# ThermoActuator-v10.net
KiCad netlist of a schematic drawn in EAGLE
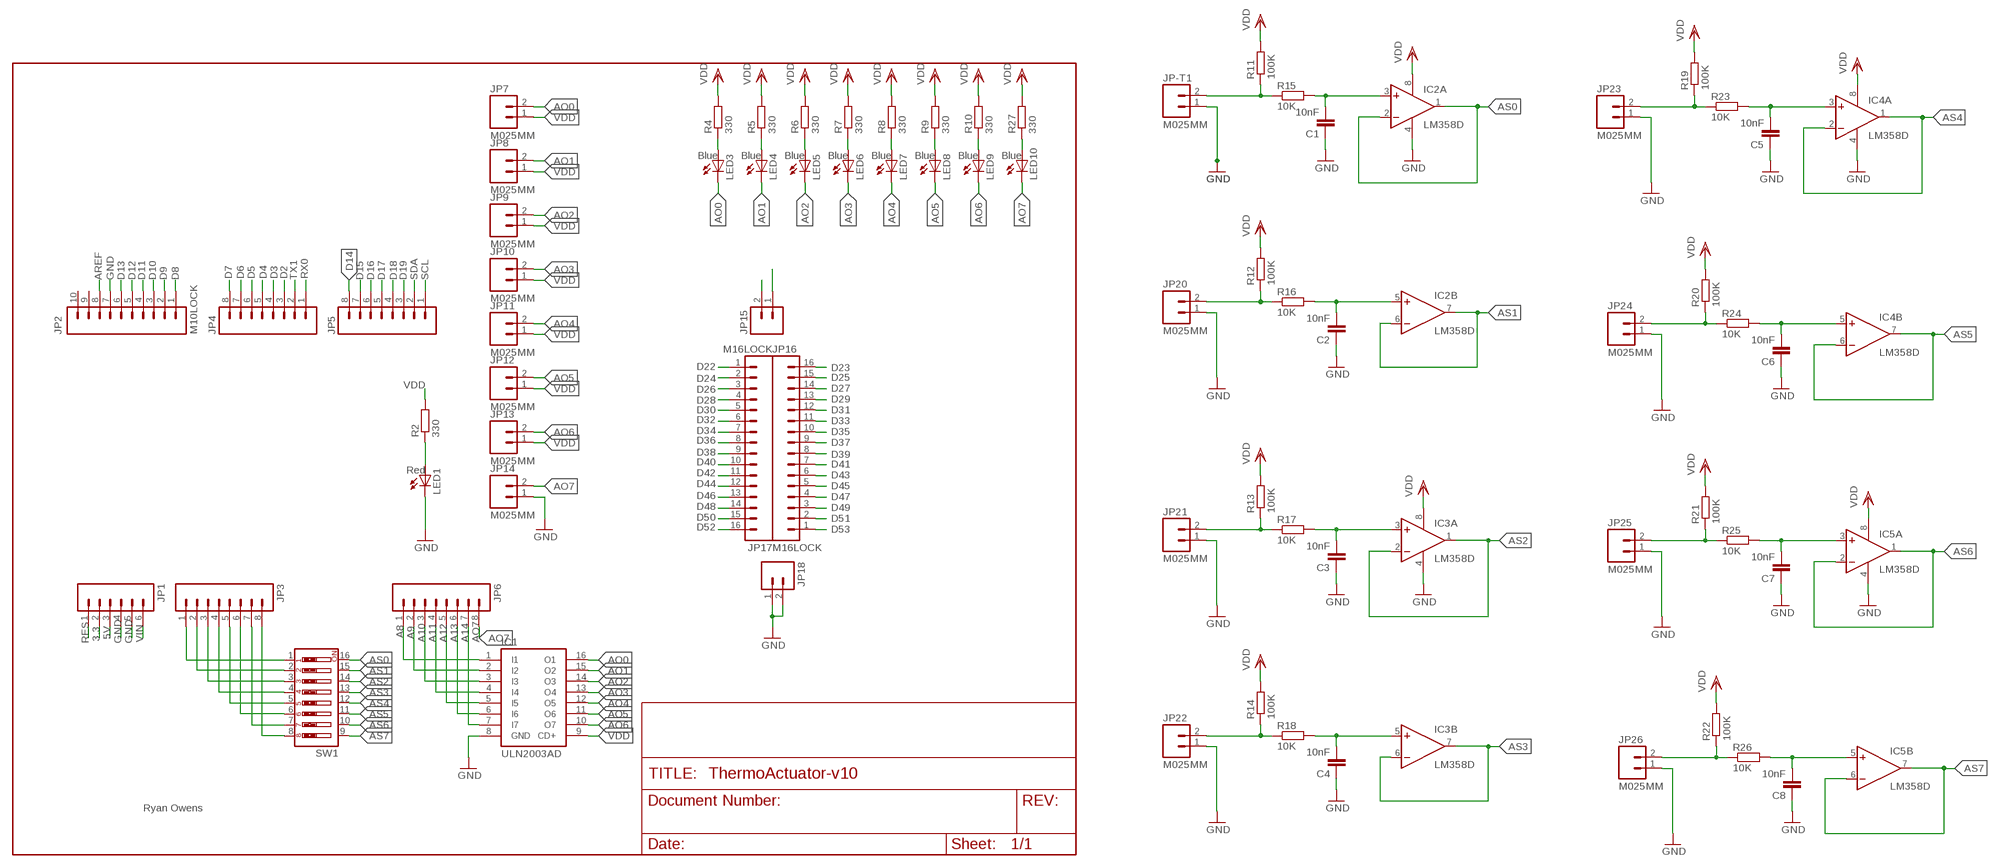
[diagram p0: schematic, sheet 1]

(export (version "E")
  (design (tool "Eeschema 10.0.6"))
  (components
    (comp (ref "C1")
      (value "10nF")
      (footprint "eagle-import:C1206")
      (libsource (lib "eagle-import") (part "C-EUC1206"))
    )
    (comp (ref "C2")
      (value "10nF")
      (footprint "eagle-import:C1206")
      (libsource (lib "eagle-import") (part "C-EUC1206"))
    )
    (comp (ref "C3")
      (value "10nF")
      (footprint "eagle-import:C1206")
      (libsource (lib "eagle-import") (part "C-EUC1206"))
    )
    (comp (ref "C4")
      (value "10nF")
      (footprint "eagle-import:C1206")
      (libsource (lib "eagle-import") (part "C-EUC1206"))
    )
    (comp (ref "C5")
      (value "10nF")
      (footprint "eagle-import:C1206")
      (libsource (lib "eagle-import") (part "C-EUC1206"))
    )
    (comp (ref "C6")
      (value "10nF")
      (footprint "eagle-import:C1206")
      (libsource (lib "eagle-import") (part "C-EUC1206"))
    )
    (comp (ref "C7")
      (value "10nF")
      (footprint "eagle-import:C1206")
      (libsource (lib "eagle-import") (part "C-EUC1206"))
    )
    (comp (ref "C8")
      (value "10nF")
      (footprint "eagle-import:C1206")
      (libsource (lib "eagle-import") (part "C-EUC1206"))
    )
    (comp (ref "IC1")
      (value "ULN2003AD")
      (footprint "eagle-import:SO16")
      (libsource (lib "eagle-import") (part "ULN2003AD"))
    )
    (comp (ref "IC2")
      (value "LM358D")
      (footprint "eagle-import:SO08")
      (libsource (lib "eagle-import") (part "LM358D"))
    )
    (comp (ref "IC3")
      (value "LM358D")
      (footprint "eagle-import:SO08")
      (libsource (lib "eagle-import") (part "LM358D"))
    )
    (comp (ref "IC4")
      (value "LM358D")
      (footprint "eagle-import:SO08")
      (libsource (lib "eagle-import") (part "LM358D"))
    )
    (comp (ref "IC5")
      (value "LM358D")
      (footprint "eagle-import:SO08")
      (libsource (lib "eagle-import") (part "LM358D"))
    )
    (comp (ref "JP-T1")
      (value "M025MM")
      (footprint "eagle-import:SCREWTERMINAL-5MM-2")
      (libsource (lib "eagle-import") (part "SparkFun-Connectors_M025MM"))
    )
    (comp (ref "JP1")
      (value "M06LOCK")
      (footprint "eagle-import:1X06_LOCK")
      (libsource (lib "eagle-import") (part "M06LOCK"))
    )
    (comp (ref "JP2")
      (value "M10LOCK")
      (footprint "eagle-import:1X10_LOCK")
      (libsource (lib "eagle-import") (part "M10LOCK"))
    )
    (comp (ref "JP3")
      (value "M08LOCK")
      (footprint "eagle-import:1X08_LOCK")
      (libsource (lib "eagle-import") (part "M08LOCK"))
    )
    (comp (ref "JP4")
      (value "M08LOCK")
      (footprint "eagle-import:1X08_LOCK")
      (libsource (lib "eagle-import") (part "M08LOCK"))
    )
    (comp (ref "JP5")
      (value "M08LOCK")
      (footprint "eagle-import:1X08_LOCK")
      (libsource (lib "eagle-import") (part "M08LOCK"))
    )
    (comp (ref "JP6")
      (value "M08LOCK")
      (footprint "eagle-import:1X08_LOCK")
      (libsource (lib "eagle-import") (part "M08LOCK"))
    )
    (comp (ref "JP7")
      (value "M025MM")
      (footprint "eagle-import:SCREWTERMINAL-5MM-2")
      (libsource (lib "eagle-import") (part "SparkFun-Connectors_M025MM"))
    )
    (comp (ref "JP8")
      (value "M025MM")
      (footprint "eagle-import:SCREWTERMINAL-5MM-2")
      (libsource (lib "eagle-import") (part "SparkFun-Connectors_M025MM"))
    )
    (comp (ref "JP9")
      (value "M025MM")
      (footprint "eagle-import:SCREWTERMINAL-5MM-2")
      (libsource (lib "eagle-import") (part "SparkFun-Connectors_M025MM"))
    )
    (comp (ref "JP10")
      (value "M025MM")
      (footprint "eagle-import:SCREWTERMINAL-5MM-2")
      (libsource (lib "eagle-import") (part "SparkFun-Connectors_M025MM"))
    )
    (comp (ref "JP11")
      (value "M025MM")
      (footprint "eagle-import:SCREWTERMINAL-5MM-2")
      (libsource (lib "eagle-import") (part "SparkFun-Connectors_M025MM"))
    )
    (comp (ref "JP12")
      (value "M025MM")
      (footprint "eagle-import:SCREWTERMINAL-5MM-2")
      (libsource (lib "eagle-import") (part "SparkFun-Connectors_M025MM"))
    )
    (comp (ref "JP13")
      (value "M025MM")
      (footprint "eagle-import:SCREWTERMINAL-5MM-2")
      (libsource (lib "eagle-import") (part "SparkFun-Connectors_M025MM"))
    )
    (comp (ref "JP14")
      (value "M025MM")
      (footprint "eagle-import:SCREWTERMINAL-5MM-2")
      (libsource (lib "eagle-import") (part "SparkFun-Connectors_M025MM"))
    )
    (comp (ref "JP15")
      (value "M02LOCK")
      (footprint "eagle-import:1X02_LOCK")
      (libsource (lib "eagle-import") (part "M02LOCK"))
    )
    (comp (ref "JP16")
      (value "M16LOCK")
      (footprint "eagle-import:1X16_LOCK")
      (libsource (lib "eagle-import") (part "M16LOCK"))
    )
    (comp (ref "JP17")
      (value "M16LOCK")
      (footprint "eagle-import:1X16_LOCK")
      (libsource (lib "eagle-import") (part "M16LOCK"))
    )
    (comp (ref "JP18")
      (value "M02LOCK")
      (footprint "eagle-import:1X02_LOCK")
      (libsource (lib "eagle-import") (part "M02LOCK"))
    )
    (comp (ref "JP20")
      (value "M025MM")
      (footprint "eagle-import:SCREWTERMINAL-5MM-2")
      (libsource (lib "eagle-import") (part "SparkFun-Connectors_M025MM"))
    )
    (comp (ref "JP21")
      (value "M025MM")
      (footprint "eagle-import:SCREWTERMINAL-5MM-2")
      (libsource (lib "eagle-import") (part "SparkFun-Connectors_M025MM"))
    )
    (comp (ref "JP22")
      (value "M025MM")
      (footprint "eagle-import:SCREWTERMINAL-5MM-2")
      (libsource (lib "eagle-import") (part "SparkFun-Connectors_M025MM"))
    )
    (comp (ref "JP23")
      (value "M025MM")
      (footprint "eagle-import:SCREWTERMINAL-5MM-2")
      (libsource (lib "eagle-import") (part "SparkFun-Connectors_M025MM"))
    )
    (comp (ref "JP24")
      (value "M025MM")
      (footprint "eagle-import:SCREWTERMINAL-5MM-2")
      (libsource (lib "eagle-import") (part "SparkFun-Connectors_M025MM"))
    )
    (comp (ref "JP25")
      (value "M025MM")
      (footprint "eagle-import:SCREWTERMINAL-5MM-2")
      (libsource (lib "eagle-import") (part "SparkFun-Connectors_M025MM"))
    )
    (comp (ref "JP26")
      (value "M025MM")
      (footprint "eagle-import:SCREWTERMINAL-5MM-2")
      (libsource (lib "eagle-import") (part "SparkFun-Connectors_M025MM"))
    )
    (comp (ref "LED1")
      (value "Red")
      (footprint "eagle-import:CHIP-LED0805")
      (libsource (lib "eagle-import") (part "LEDCHIP-LED0805"))
    )
    (comp (ref "LED3")
      (value "Blue")
      (footprint "eagle-import:CHIP-LED0805")
      (libsource (lib "eagle-import") (part "LEDCHIP-LED0805"))
    )
    (comp (ref "LED4")
      (value "Blue")
      (footprint "eagle-import:CHIP-LED0805")
      (libsource (lib "eagle-import") (part "LEDCHIP-LED0805"))
    )
    (comp (ref "LED5")
      (value "Blue")
      (footprint "eagle-import:CHIP-LED0805")
      (libsource (lib "eagle-import") (part "LEDCHIP-LED0805"))
    )
    (comp (ref "LED6")
      (value "Blue")
      (footprint "eagle-import:CHIP-LED0805")
      (libsource (lib "eagle-import") (part "LEDCHIP-LED0805"))
    )
    (comp (ref "LED7")
      (value "Blue")
      (footprint "eagle-import:CHIP-LED0805")
      (libsource (lib "eagle-import") (part "LEDCHIP-LED0805"))
    )
    (comp (ref "LED8")
      (value "Blue")
      (footprint "eagle-import:CHIP-LED0805")
      (libsource (lib "eagle-import") (part "LEDCHIP-LED0805"))
    )
    (comp (ref "LED9")
      (value "Blue")
      (footprint "eagle-import:CHIP-LED0805")
      (libsource (lib "eagle-import") (part "LEDCHIP-LED0805"))
    )
    (comp (ref "LED10")
      (value "Blue")
      (footprint "eagle-import:CHIP-LED0805")
      (libsource (lib "eagle-import") (part "LEDCHIP-LED0805"))
    )
    (comp (ref "R2")
      (value "330")
      (footprint "eagle-import:R0805")
      (libsource (lib "eagle-import") (part "R-EU_R0805"))
    )
    (comp (ref "R4")
      (value "330")
      (footprint "eagle-import:R0805")
      (libsource (lib "eagle-import") (part "R-EU_R0805"))
    )
    (comp (ref "R5")
      (value "330")
      (footprint "eagle-import:R0805")
      (libsource (lib "eagle-import") (part "R-EU_R0805"))
    )
    (comp (ref "R6")
      (value "330")
      (footprint "eagle-import:R0805")
      (libsource (lib "eagle-import") (part "R-EU_R0805"))
    )
    (comp (ref "R7")
      (value "330")
      (footprint "eagle-import:R0805")
      (libsource (lib "eagle-import") (part "R-EU_R0805"))
    )
    (comp (ref "R8")
      (value "330")
      (footprint "eagle-import:R0805")
      (libsource (lib "eagle-import") (part "R-EU_R0805"))
    )
    (comp (ref "R9")
      (value "330")
      (footprint "eagle-import:R0805")
      (libsource (lib "eagle-import") (part "R-EU_R0805"))
    )
    (comp (ref "R10")
      (value "330")
      (footprint "eagle-import:R0805")
      (libsource (lib "eagle-import") (part "R-EU_R0805"))
    )
    (comp (ref "R11")
      (value "100K")
      (footprint "eagle-import:R0805")
      (libsource (lib "eagle-import") (part "R-EU_R0805"))
    )
    (comp (ref "R12")
      (value "100K")
      (footprint "eagle-import:R0805")
      (libsource (lib "eagle-import") (part "R-EU_R0805"))
    )
    (comp (ref "R13")
      (value "100K")
      (footprint "eagle-import:R0805")
      (libsource (lib "eagle-import") (part "R-EU_R0805"))
    )
    (comp (ref "R14")
      (value "100K")
      (footprint "eagle-import:R0805")
      (libsource (lib "eagle-import") (part "R-EU_R0805"))
    )
    (comp (ref "R15")
      (value "10K")
      (footprint "eagle-import:R1206")
      (libsource (lib "eagle-import") (part "R-EU_R1206"))
    )
    (comp (ref "R16")
      (value "10K")
      (footprint "eagle-import:R1206")
      (libsource (lib "eagle-import") (part "R-EU_R1206"))
    )
    (comp (ref "R17")
      (value "10K")
      (footprint "eagle-import:R1206")
      (libsource (lib "eagle-import") (part "R-EU_R1206"))
    )
    (comp (ref "R18")
      (value "10K")
      (footprint "eagle-import:R1206")
      (libsource (lib "eagle-import") (part "R-EU_R1206"))
    )
    (comp (ref "R19")
      (value "100K")
      (footprint "eagle-import:R0805")
      (libsource (lib "eagle-import") (part "R-EU_R0805"))
    )
    (comp (ref "R20")
      (value "100K")
      (footprint "eagle-import:R0805")
      (libsource (lib "eagle-import") (part "R-EU_R0805"))
    )
    (comp (ref "R21")
      (value "100K")
      (footprint "eagle-import:R0805")
      (libsource (lib "eagle-import") (part "R-EU_R0805"))
    )
    (comp (ref "R22")
      (value "100K")
      (footprint "eagle-import:R0805")
      (libsource (lib "eagle-import") (part "R-EU_R0805"))
    )
    (comp (ref "R23")
      (value "10K")
      (footprint "eagle-import:R1206")
      (libsource (lib "eagle-import") (part "R-EU_R1206"))
    )
    (comp (ref "R24")
      (value "10K")
      (footprint "eagle-import:R1206")
      (libsource (lib "eagle-import") (part "R-EU_R1206"))
    )
    (comp (ref "R25")
      (value "10K")
      (footprint "eagle-import:R1206")
      (libsource (lib "eagle-import") (part "R-EU_R1206"))
    )
    (comp (ref "R26")
      (value "10K")
      (footprint "eagle-import:R1206")
      (libsource (lib "eagle-import") (part "R-EU_R1206"))
    )
    (comp (ref "R27")
      (value "330")
      (footprint "eagle-import:R0805")
      (libsource (lib "eagle-import") (part "R-EU_R0805"))
    )
    (comp (ref "SW1")
      (value "SW_DIP-8")
      (footprint "eagle-import:EDG-08")
      (libsource (lib "eagle-import") (part "SW_DIP-8"))
    )
  )
  (nets
    (net (code "1") (name "/3.3") (class "Default")
      (node (ref "JP1") (pin "2") (pinfunction "2_2") (pintype "passive"))
    )
    (net (code "2") (name "/5V") (class "Default")
      (node (ref "JP1") (pin "3") (pinfunction "3_3") (pintype "passive"))
    )
    (net (code "3") (name "/A8") (class "Default")
      (node (ref "IC1") (pin "1") (pinfunction "I1_1") (pintype "input"))
      (node (ref "JP6") (pin "1") (pinfunction "1_1") (pintype "passive"))
    )
    (net (code "4") (name "/A9") (class "Default")
      (node (ref "IC1") (pin "2") (pinfunction "I2_2") (pintype "input"))
      (node (ref "JP6") (pin "2") (pinfunction "2_2") (pintype "passive"))
    )
    (net (code "5") (name "/A10") (class "Default")
      (node (ref "IC1") (pin "3") (pinfunction "I3_3") (pintype "input"))
      (node (ref "JP6") (pin "3") (pinfunction "3_3") (pintype "passive"))
    )
    (net (code "6") (name "/A11") (class "Default")
      (node (ref "IC1") (pin "4") (pinfunction "I4_4") (pintype "input"))
      (node (ref "JP6") (pin "4") (pinfunction "4_4") (pintype "passive"))
    )
    (net (code "7") (name "/A12") (class "Default")
      (node (ref "IC1") (pin "5") (pinfunction "I5_5") (pintype "input"))
      (node (ref "JP6") (pin "5") (pinfunction "5_5") (pintype "passive"))
    )
    (net (code "8") (name "/A13") (class "Default")
      (node (ref "IC1") (pin "6") (pinfunction "I6_6") (pintype "input"))
      (node (ref "JP6") (pin "6") (pinfunction "6_6") (pintype "passive"))
    )
    (net (code "9") (name "/A14") (class "Default")
      (node (ref "IC1") (pin "7") (pinfunction "I7_7") (pintype "input"))
      (node (ref "JP6") (pin "7") (pinfunction "7_7") (pintype "passive"))
    )
    (net (code "10") (name "/AREF") (class "Default")
      (node (ref "JP2") (pin "8") (pinfunction "8_8") (pintype "passive"))
    )
    (net (code "11") (name "/D2") (class "Default")
      (node (ref "JP4") (pin "3") (pinfunction "3_3") (pintype "passive"))
    )
    (net (code "12") (name "/D3") (class "Default")
      (node (ref "JP4") (pin "4") (pinfunction "4_4") (pintype "passive"))
    )
    (net (code "13") (name "/D4") (class "Default")
      (node (ref "JP4") (pin "5") (pinfunction "5_5") (pintype "passive"))
    )
    (net (code "14") (name "/D5") (class "Default")
      (node (ref "JP4") (pin "6") (pinfunction "6_6") (pintype "passive"))
    )
    (net (code "15") (name "/D6") (class "Default")
      (node (ref "JP4") (pin "7") (pinfunction "7_7") (pintype "passive"))
    )
    (net (code "16") (name "/D7") (class "Default")
      (node (ref "JP4") (pin "8") (pinfunction "8_8") (pintype "passive"))
    )
    (net (code "17") (name "/D8") (class "Default")
      (node (ref "JP2") (pin "1") (pinfunction "1_1") (pintype "passive"))
    )
    (net (code "18") (name "/D9") (class "Default")
      (node (ref "JP2") (pin "2") (pinfunction "2_2") (pintype "passive"))
    )
    (net (code "19") (name "/D10") (class "Default")
      (node (ref "JP2") (pin "3") (pinfunction "3_3") (pintype "passive"))
    )
    (net (code "20") (name "/D11") (class "Default")
      (node (ref "JP2") (pin "4") (pinfunction "4_4") (pintype "passive"))
    )
    (net (code "21") (name "/D12") (class "Default")
      (node (ref "JP2") (pin "5") (pinfunction "5_5") (pintype "passive"))
    )
    (net (code "22") (name "/D13") (class "Default")
      (node (ref "JP2") (pin "6") (pinfunction "6_6") (pintype "passive"))
    )
    (net (code "23") (name "/D15") (class "Default")
      (node (ref "JP5") (pin "7") (pinfunction "7_7") (pintype "passive"))
    )
    (net (code "24") (name "/D16") (class "Default")
      (node (ref "JP5") (pin "6") (pinfunction "6_6") (pintype "passive"))
    )
    (net (code "25") (name "/D17") (class "Default")
      (node (ref "JP5") (pin "5") (pinfunction "5_5") (pintype "passive"))
    )
    (net (code "26") (name "/D18") (class "Default")
      (node (ref "JP5") (pin "4") (pinfunction "4_4") (pintype "passive"))
    )
    (net (code "27") (name "/D19") (class "Default")
      (node (ref "JP5") (pin "3") (pinfunction "3_3") (pintype "passive"))
    )
    (net (code "28") (name "/D22") (class "Default")
      (node (ref "JP17") (pin "1") (pinfunction "1_1") (pintype "passive"))
    )
    (net (code "29") (name "/D23") (class "Default")
      (node (ref "JP16") (pin "16") (pinfunction "16_16") (pintype "passive"))
    )
    (net (code "30") (name "/D24") (class "Default")
      (node (ref "JP17") (pin "2") (pinfunction "2_2") (pintype "passive"))
    )
    (net (code "31") (name "/D25") (class "Default")
      (node (ref "JP16") (pin "15") (pinfunction "15_15") (pintype "passive"))
    )
    (net (code "32") (name "/D26") (class "Default")
      (node (ref "JP17") (pin "3") (pinfunction "3_3") (pintype "passive"))
    )
    (net (code "33") (name "/D27") (class "Default")
      (node (ref "JP16") (pin "14") (pinfunction "14_14") (pintype "passive"))
    )
    (net (code "34") (name "/D28") (class "Default")
      (node (ref "JP17") (pin "4") (pinfunction "4_4") (pintype "passive"))
    )
    (net (code "35") (name "/D29") (class "Default")
      (node (ref "JP16") (pin "13") (pinfunction "13_13") (pintype "passive"))
    )
    (net (code "36") (name "/D30") (class "Default")
      (node (ref "JP17") (pin "5") (pinfunction "5_5") (pintype "passive"))
    )
    (net (code "37") (name "/D31") (class "Default")
      (node (ref "JP16") (pin "12") (pinfunction "12_12") (pintype "passive"))
    )
    (net (code "38") (name "/D32") (class "Default")
      (node (ref "JP17") (pin "6") (pinfunction "6_6") (pintype "passive"))
    )
    (net (code "39") (name "/D33") (class "Default")
      (node (ref "JP16") (pin "11") (pinfunction "11_11") (pintype "passive"))
    )
    (net (code "40") (name "/D34") (class "Default")
      (node (ref "JP17") (pin "7") (pinfunction "7_7") (pintype "passive"))
    )
    (net (code "41") (name "/D35") (class "Default")
      (node (ref "JP16") (pin "10") (pinfunction "10_10") (pintype "passive"))
    )
    (net (code "42") (name "/D36") (class "Default")
      (node (ref "JP17") (pin "8") (pinfunction "8_8") (pintype "passive"))
    )
    (net (code "43") (name "/D37") (class "Default")
      (node (ref "JP16") (pin "9") (pinfunction "9_9") (pintype "passive"))
    )
    (net (code "44") (name "/D38") (class "Default")
      (node (ref "JP17") (pin "9") (pinfunction "9_9") (pintype "passive"))
    )
    (net (code "45") (name "/D39") (class "Default")
      (node (ref "JP16") (pin "8") (pinfunction "8_8") (pintype "passive"))
    )
    (net (code "46") (name "/D40") (class "Default")
      (node (ref "JP17") (pin "10") (pinfunction "10_10") (pintype "passive"))
    )
    (net (code "47") (name "/D41") (class "Default")
      (node (ref "JP16") (pin "7") (pinfunction "7_7") (pintype "passive"))
    )
    (net (code "48") (name "/D42") (class "Default")
      (node (ref "JP17") (pin "11") (pinfunction "11_11") (pintype "passive"))
    )
    (net (code "49") (name "/D43") (class "Default")
      (node (ref "JP16") (pin "6") (pinfunction "6_6") (pintype "passive"))
    )
    (net (code "50") (name "/D44") (class "Default")
      (node (ref "JP17") (pin "12") (pinfunction "12_12") (pintype "passive"))
    )
    (net (code "51") (name "/D45") (class "Default")
      (node (ref "JP16") (pin "5") (pinfunction "5_5") (pintype "passive"))
    )
    (net (code "52") (name "/D46") (class "Default")
      (node (ref "JP17") (pin "13") (pinfunction "13_13") (pintype "passive"))
    )
    (net (code "53") (name "/D47") (class "Default")
      (node (ref "JP16") (pin "4") (pinfunction "4_4") (pintype "passive"))
    )
    (net (code "54") (name "/D48") (class "Default")
      (node (ref "JP17") (pin "14") (pinfunction "14_14") (pintype "passive"))
    )
    (net (code "55") (name "/D49") (class "Default")
      (node (ref "JP16") (pin "3") (pinfunction "3_3") (pintype "passive"))
    )
    (net (code "56") (name "/D50") (class "Default")
      (node (ref "JP17") (pin "15") (pinfunction "15_15") (pintype "passive"))
    )
    (net (code "57") (name "/D51") (class "Default")
      (node (ref "JP16") (pin "2") (pinfunction "2_2") (pintype "passive"))
    )
    (net (code "58") (name "/D52") (class "Default")
      (node (ref "JP17") (pin "16") (pinfunction "16_16") (pintype "passive"))
    )
    (net (code "59") (name "/D53") (class "Default")
      (node (ref "JP16") (pin "1") (pinfunction "1_1") (pintype "passive"))
    )
    (net (code "60") (name "/RES") (class "Default")
      (node (ref "JP1") (pin "1") (pinfunction "1_1") (pintype "passive"))
    )
    (net (code "61") (name "/RX0") (class "Default")
      (node (ref "JP4") (pin "1") (pinfunction "1_1") (pintype "passive"))
    )
    (net (code "62") (name "/SCL") (class "Default")
      (node (ref "JP5") (pin "1") (pinfunction "1_1") (pintype "passive"))
    )
    (net (code "63") (name "/SDA") (class "Default")
      (node (ref "JP5") (pin "2") (pinfunction "2_2") (pintype "passive"))
    )
    (net (code "64") (name "/TX1") (class "Default")
      (node (ref "JP4") (pin "2") (pinfunction "2_2") (pintype "passive"))
    )
    (net (code "65") (name "/VIN") (class "Default")
      (node (ref "JP1") (pin "6") (pinfunction "6_6") (pintype "passive"))
    )
    (net (code "66") (name "AO0") (class "Default")
      (node (ref "IC1") (pin "16") (pinfunction "O1_16") (pintype "open_collector"))
      (node (ref "JP7") (pin "2") (pinfunction "2_2") (pintype "passive"))
      (node (ref "LED3") (pin "C") (pinfunction "C_C") (pintype "passive"))
    )
    (net (code "67") (name "AO1") (class "Default")
      (node (ref "IC1") (pin "15") (pinfunction "O2_15") (pintype "open_collector"))
      (node (ref "JP8") (pin "2") (pinfunction "2_2") (pintype "passive"))
      (node (ref "LED4") (pin "C") (pinfunction "C_C") (pintype "passive"))
    )
    (net (code "68") (name "AO2") (class "Default")
      (node (ref "IC1") (pin "14") (pinfunction "O3_14") (pintype "open_collector"))
      (node (ref "JP9") (pin "2") (pinfunction "2_2") (pintype "passive"))
      (node (ref "LED5") (pin "C") (pinfunction "C_C") (pintype "passive"))
    )
    (net (code "69") (name "AO3") (class "Default")
      (node (ref "IC1") (pin "13") (pinfunction "O4_13") (pintype "open_collector"))
      (node (ref "JP10") (pin "2") (pinfunction "2_2") (pintype "passive"))
      (node (ref "LED6") (pin "C") (pinfunction "C_C") (pintype "passive"))
    )
    (net (code "70") (name "AO4") (class "Default")
      (node (ref "IC1") (pin "12") (pinfunction "O5_12") (pintype "open_collector"))
      (node (ref "JP11") (pin "2") (pinfunction "2_2") (pintype "passive"))
      (node (ref "LED7") (pin "C") (pinfunction "C_C") (pintype "passive"))
    )
    (net (code "71") (name "AO5") (class "Default")
      (node (ref "IC1") (pin "11") (pinfunction "O6_11") (pintype "open_collector"))
      (node (ref "JP12") (pin "2") (pinfunction "2_2") (pintype "passive"))
      (node (ref "LED8") (pin "C") (pinfunction "C_C") (pintype "passive"))
    )
    (net (code "72") (name "AO6") (class "Default")
      (node (ref "IC1") (pin "10") (pinfunction "O7_10") (pintype "open_collector"))
      (node (ref "JP13") (pin "2") (pinfunction "2_2") (pintype "passive"))
      (node (ref "LED9") (pin "C") (pinfunction "C_C") (pintype "passive"))
    )
    (net (code "73") (name "AO7") (class "Default")
      (node (ref "JP14") (pin "2") (pinfunction "2_2") (pintype "passive"))
      (node (ref "JP6") (pin "8") (pinfunction "8_8") (pintype "passive"))
      (node (ref "LED10") (pin "C") (pinfunction "C_C") (pintype "passive"))
    )
    (net (code "74") (name "AS0") (class "Default")
      (node (ref "IC2") (pin "1") (pinfunction "OUT_1") (pintype "output"))
      (node (ref "IC2") (pin "2") (pinfunction "-IN_2") (pintype "input"))
      (node (ref "SW1") (pin "16") (pinfunction "16_16") (pintype "passive"))
    )
    (net (code "75") (name "AS1") (class "Default")
      (node (ref "IC2") (pin "6") (pinfunction "-IN_6") (pintype "input"))
      (node (ref "IC2") (pin "7") (pinfunction "OUT_7") (pintype "output"))
      (node (ref "SW1") (pin "15") (pinfunction "15_15") (pintype "passive"))
    )
    (net (code "76") (name "AS2") (class "Default")
      (node (ref "IC3") (pin "1") (pinfunction "OUT_1") (pintype "output"))
      (node (ref "IC3") (pin "2") (pinfunction "-IN_2") (pintype "input"))
      (node (ref "SW1") (pin "14") (pinfunction "14_14") (pintype "passive"))
    )
    (net (code "77") (name "AS3") (class "Default")
      (node (ref "IC3") (pin "6") (pinfunction "-IN_6") (pintype "input"))
      (node (ref "IC3") (pin "7") (pinfunction "OUT_7") (pintype "output"))
      (node (ref "SW1") (pin "13") (pinfunction "13_13") (pintype "passive"))
    )
    (net (code "78") (name "AS4") (class "Default")
      (node (ref "IC4") (pin "1") (pinfunction "OUT_1") (pintype "output"))
      (node (ref "IC4") (pin "2") (pinfunction "-IN_2") (pintype "input"))
      (node (ref "SW1") (pin "12") (pinfunction "12_12") (pintype "passive"))
    )
    (net (code "79") (name "AS5") (class "Default")
      (node (ref "IC4") (pin "6") (pinfunction "-IN_6") (pintype "input"))
      (node (ref "IC4") (pin "7") (pinfunction "OUT_7") (pintype "output"))
      (node (ref "SW1") (pin "11") (pinfunction "11_11") (pintype "passive"))
    )
    (net (code "80") (name "AS6") (class "Default")
      (node (ref "IC5") (pin "1") (pinfunction "OUT_1") (pintype "output"))
      (node (ref "IC5") (pin "2") (pinfunction "-IN_2") (pintype "input"))
      (node (ref "SW1") (pin "10") (pinfunction "10_10") (pintype "passive"))
    )
    (net (code "81") (name "AS7") (class "Default")
      (node (ref "IC5") (pin "6") (pinfunction "-IN_6") (pintype "input"))
      (node (ref "IC5") (pin "7") (pinfunction "OUT_7") (pintype "output"))
      (node (ref "SW1") (pin "9") (pinfunction "9_9") (pintype "passive"))
    )
    (net (code "82") (name "D14") (class "Default")
      (node (ref "JP5") (pin "8") (pinfunction "8_8") (pintype "passive"))
    )
    (net (code "83") (name "GND") (class "Default")
      (node (ref "C1") (pin "1") (pinfunction "1_1") (pintype "passive"))
      (node (ref "C2") (pin "1") (pinfunction "1_1") (pintype "passive"))
      (node (ref "C3") (pin "1") (pinfunction "1_1") (pintype "passive"))
      (node (ref "C4") (pin "1") (pinfunction "1_1") (pintype "passive"))
      (node (ref "C5") (pin "1") (pinfunction "1_1") (pintype "passive"))
      (node (ref "C6") (pin "1") (pinfunction "1_1") (pintype "passive"))
      (node (ref "C7") (pin "1") (pinfunction "1_1") (pintype "passive"))
      (node (ref "C8") (pin "1") (pinfunction "1_1") (pintype "passive"))
      (node (ref "IC1") (pin "8") (pinfunction "GND_8") (pintype "power_in"))
      (node (ref "IC2") (pin "4") (pinfunction "V-_4") (pintype "power_in"))
      (node (ref "IC3") (pin "4") (pinfunction "V-_4") (pintype "power_in"))
      (node (ref "IC4") (pin "4") (pinfunction "V-_4") (pintype "power_in"))
      (node (ref "IC5") (pin "4") (pinfunction "V-_4") (pintype "power_in"))
      (node (ref "JP-T1") (pin "1") (pinfunction "1_1") (pintype "passive"))
      (node (ref "JP1") (pin "4") (pinfunction "4_4") (pintype "passive"))
      (node (ref "JP1") (pin "5") (pinfunction "5_5") (pintype "passive"))
      (node (ref "JP14") (pin "1") (pinfunction "1_1") (pintype "passive"))
      (node (ref "JP18") (pin "1") (pinfunction "1_1") (pintype "passive"))
      (node (ref "JP18") (pin "2") (pinfunction "2_2") (pintype "passive"))
      (node (ref "JP2") (pin "7") (pinfunction "7_7") (pintype "passive"))
      (node (ref "JP20") (pin "1") (pinfunction "1_1") (pintype "passive"))
      (node (ref "JP21") (pin "1") (pinfunction "1_1") (pintype "passive"))
      (node (ref "JP22") (pin "1") (pinfunction "1_1") (pintype "passive"))
      (node (ref "JP23") (pin "1") (pinfunction "1_1") (pintype "passive"))
      (node (ref "JP24") (pin "1") (pinfunction "1_1") (pintype "passive"))
      (node (ref "JP25") (pin "1") (pinfunction "1_1") (pintype "passive"))
      (node (ref "JP26") (pin "1") (pinfunction "1_1") (pintype "passive"))
      (node (ref "LED1") (pin "C") (pinfunction "C_C") (pintype "passive"))
    )
    (net (code "84") (name "Net-(IC2A-+IN)") (class "Default")
      (node (ref "C1") (pin "2") (pinfunction "2_2") (pintype "passive"))
      (node (ref "IC2") (pin "3") (pinfunction "+IN_3") (pintype "input"))
      (node (ref "R15") (pin "2") (pinfunction "2_2") (pintype "passive"))
    )
    (net (code "85") (name "Net-(IC2B-+IN)") (class "Default")
      (node (ref "C2") (pin "2") (pinfunction "2_2") (pintype "passive"))
      (node (ref "IC2") (pin "5") (pinfunction "+IN_5") (pintype "input"))
      (node (ref "R16") (pin "2") (pinfunction "2_2") (pintype "passive"))
    )
    (net (code "86") (name "Net-(IC3A-+IN)") (class "Default")
      (node (ref "C3") (pin "2") (pinfunction "2_2") (pintype "passive"))
      (node (ref "IC3") (pin "3") (pinfunction "+IN_3") (pintype "input"))
      (node (ref "R17") (pin "2") (pinfunction "2_2") (pintype "passive"))
    )
    (net (code "87") (name "Net-(IC3B-+IN)") (class "Default")
      (node (ref "C4") (pin "2") (pinfunction "2_2") (pintype "passive"))
      (node (ref "IC3") (pin "5") (pinfunction "+IN_5") (pintype "input"))
      (node (ref "R18") (pin "2") (pinfunction "2_2") (pintype "passive"))
    )
    (net (code "88") (name "Net-(IC4A-+IN)") (class "Default")
      (node (ref "C5") (pin "2") (pinfunction "2_2") (pintype "passive"))
      (node (ref "IC4") (pin "3") (pinfunction "+IN_3") (pintype "input"))
      (node (ref "R23") (pin "2") (pinfunction "2_2") (pintype "passive"))
    )
    (net (code "89") (name "Net-(IC4B-+IN)") (class "Default")
      (node (ref "C6") (pin "2") (pinfunction "2_2") (pintype "passive"))
      (node (ref "IC4") (pin "5") (pinfunction "+IN_5") (pintype "input"))
      (node (ref "R24") (pin "2") (pinfunction "2_2") (pintype "passive"))
    )
    (net (code "90") (name "Net-(IC5A-+IN)") (class "Default")
      (node (ref "C7") (pin "2") (pinfunction "2_2") (pintype "passive"))
      (node (ref "IC5") (pin "3") (pinfunction "+IN_3") (pintype "input"))
      (node (ref "R25") (pin "2") (pinfunction "2_2") (pintype "passive"))
    )
    (net (code "91") (name "Net-(IC5B-+IN)") (class "Default")
      (node (ref "C8") (pin "2") (pinfunction "2_2") (pintype "passive"))
      (node (ref "IC5") (pin "5") (pinfunction "+IN_5") (pintype "input"))
      (node (ref "R26") (pin "2") (pinfunction "2_2") (pintype "passive"))
    )
    (net (code "92") (name "Net-(JP-T1-Pad2)") (class "Default")
      (node (ref "JP-T1") (pin "2") (pinfunction "2_2") (pintype "passive"))
      (node (ref "R11") (pin "1") (pinfunction "1_1") (pintype "passive"))
      (node (ref "R15") (pin "1") (pinfunction "1_1") (pintype "passive"))
    )
    (net (code "93") (name "Net-(JP3-Pad1)") (class "Default")
      (node (ref "JP3") (pin "1") (pinfunction "1_1") (pintype "passive"))
      (node (ref "SW1") (pin "1") (pinfunction "1_1") (pintype "passive"))
    )
    (net (code "94") (name "Net-(JP3-Pad2)") (class "Default")
      (node (ref "JP3") (pin "2") (pinfunction "2_2") (pintype "passive"))
      (node (ref "SW1") (pin "2") (pinfunction "2_2") (pintype "passive"))
    )
    (net (code "95") (name "Net-(JP3-Pad3)") (class "Default")
      (node (ref "JP3") (pin "3") (pinfunction "3_3") (pintype "passive"))
      (node (ref "SW1") (pin "3") (pinfunction "3_3") (pintype "passive"))
    )
    (net (code "96") (name "Net-(JP3-Pad4)") (class "Default")
      (node (ref "JP3") (pin "4") (pinfunction "4_4") (pintype "passive"))
      (node (ref "SW1") (pin "4") (pinfunction "4_4") (pintype "passive"))
    )
    (net (code "97") (name "Net-(JP3-Pad5)") (class "Default")
      (node (ref "JP3") (pin "5") (pinfunction "5_5") (pintype "passive"))
      (node (ref "SW1") (pin "5") (pinfunction "5_5") (pintype "passive"))
    )
    (net (code "98") (name "Net-(JP3-Pad6)") (class "Default")
      (node (ref "JP3") (pin "6") (pinfunction "6_6") (pintype "passive"))
      (node (ref "SW1") (pin "6") (pinfunction "6_6") (pintype "passive"))
    )
    (net (code "99") (name "Net-(JP3-Pad7)") (class "Default")
      (node (ref "JP3") (pin "7") (pinfunction "7_7") (pintype "passive"))
      (node (ref "SW1") (pin "7") (pinfunction "7_7") (pintype "passive"))
    )
    (net (code "100") (name "Net-(JP3-Pad8)") (class "Default")
      (node (ref "JP3") (pin "8") (pinfunction "8_8") (pintype "passive"))
      (node (ref "SW1") (pin "8") (pinfunction "8_8") (pintype "passive"))
    )
    (net (code "101") (name "Net-(JP20-Pad2)") (class "Default")
      (node (ref "JP20") (pin "2") (pinfunction "2_2") (pintype "passive"))
      (node (ref "R12") (pin "1") (pinfunction "1_1") (pintype "passive"))
      (node (ref "R16") (pin "1") (pinfunction "1_1") (pintype "passive"))
    )
    (net (code "102") (name "Net-(JP21-Pad2)") (class "Default")
      (node (ref "JP21") (pin "2") (pinfunction "2_2") (pintype "passive"))
      (node (ref "R13") (pin "1") (pinfunction "1_1") (pintype "passive"))
      (node (ref "R17") (pin "1") (pinfunction "1_1") (pintype "passive"))
    )
    (net (code "103") (name "Net-(JP22-Pad2)") (class "Default")
      (node (ref "JP22") (pin "2") (pinfunction "2_2") (pintype "passive"))
      (node (ref "R14") (pin "1") (pinfunction "1_1") (pintype "passive"))
      (node (ref "R18") (pin "1") (pinfunction "1_1") (pintype "passive"))
    )
    (net (code "104") (name "Net-(JP23-Pad2)") (class "Default")
      (node (ref "JP23") (pin "2") (pinfunction "2_2") (pintype "passive"))
      (node (ref "R19") (pin "1") (pinfunction "1_1") (pintype "passive"))
      (node (ref "R23") (pin "1") (pinfunction "1_1") (pintype "passive"))
    )
    (net (code "105") (name "Net-(JP24-Pad2)") (class "Default")
      (node (ref "JP24") (pin "2") (pinfunction "2_2") (pintype "passive"))
      (node (ref "R20") (pin "1") (pinfunction "1_1") (pintype "passive"))
      (node (ref "R24") (pin "1") (pinfunction "1_1") (pintype "passive"))
    )
    (net (code "106") (name "Net-(JP25-Pad2)") (class "Default")
      (node (ref "JP25") (pin "2") (pinfunction "2_2") (pintype "passive"))
      (node (ref "R21") (pin "1") (pinfunction "1_1") (pintype "passive"))
      (node (ref "R25") (pin "1") (pinfunction "1_1") (pintype "passive"))
    )
    (net (code "107") (name "Net-(JP26-Pad2)") (class "Default")
      (node (ref "JP26") (pin "2") (pinfunction "2_2") (pintype "passive"))
      (node (ref "R22") (pin "1") (pinfunction "1_1") (pintype "passive"))
      (node (ref "R26") (pin "1") (pinfunction "1_1") (pintype "passive"))
    )
    (net (code "108") (name "Net-(LED1-PadA)") (class "Default")
      (node (ref "LED1") (pin "A") (pinfunction "A_A") (pintype "passive"))
      (node (ref "R2") (pin "1") (pinfunction "1_1") (pintype "passive"))
    )
    (net (code "109") (name "Net-(LED3-PadA)") (class "Default")
      (node (ref "LED3") (pin "A") (pinfunction "A_A") (pintype "passive"))
      (node (ref "R4") (pin "1") (pinfunction "1_1") (pintype "passive"))
    )
    (net (code "110") (name "Net-(LED4-PadA)") (class "Default")
      (node (ref "LED4") (pin "A") (pinfunction "A_A") (pintype "passive"))
      (node (ref "R5") (pin "1") (pinfunction "1_1") (pintype "passive"))
    )
    (net (code "111") (name "Net-(LED5-PadA)") (class "Default")
      (node (ref "LED5") (pin "A") (pinfunction "A_A") (pintype "passive"))
      (node (ref "R6") (pin "1") (pinfunction "1_1") (pintype "passive"))
    )
    (net (code "112") (name "Net-(LED6-PadA)") (class "Default")
      (node (ref "LED6") (pin "A") (pinfunction "A_A") (pintype "passive"))
      (node (ref "R7") (pin "1") (pinfunction "1_1") (pintype "passive"))
    )
    (net (code "113") (name "Net-(LED7-PadA)") (class "Default")
      (node (ref "LED7") (pin "A") (pinfunction "A_A") (pintype "passive"))
      (node (ref "R8") (pin "1") (pinfunction "1_1") (pintype "passive"))
    )
    (net (code "114") (name "Net-(LED8-PadA)") (class "Default")
      (node (ref "LED8") (pin "A") (pinfunction "A_A") (pintype "passive"))
      (node (ref "R9") (pin "1") (pinfunction "1_1") (pintype "passive"))
    )
    (net (code "115") (name "Net-(LED9-PadA)") (class "Default")
      (node (ref "LED9") (pin "A") (pinfunction "A_A") (pintype "passive"))
      (node (ref "R10") (pin "1") (pinfunction "1_1") (pintype "passive"))
    )
    (net (code "116") (name "Net-(LED10-PadA)") (class "Default")
      (node (ref "LED10") (pin "A") (pinfunction "A_A") (pintype "passive"))
      (node (ref "R27") (pin "1") (pinfunction "1_1") (pintype "passive"))
    )
    (net (code "117") (name "VDD") (class "Default")
      (node (ref "IC1") (pin "9") (pinfunction "CD+_9") (pintype "passive"))
      (node (ref "IC2") (pin "8") (pinfunction "V+_8") (pintype "power_in"))
      (node (ref "IC3") (pin "8") (pinfunction "V+_8") (pintype "power_in"))
      (node (ref "IC4") (pin "8") (pinfunction "V+_8") (pintype "power_in"))
      (node (ref "IC5") (pin "8") (pinfunction "V+_8") (pintype "power_in"))
      (node (ref "JP10") (pin "1") (pinfunction "1_1") (pintype "passive"))
      (node (ref "JP11") (pin "1") (pinfunction "1_1") (pintype "passive"))
      (node (ref "JP12") (pin "1") (pinfunction "1_1") (pintype "passive"))
      (node (ref "JP13") (pin "1") (pinfunction "1_1") (pintype "passive"))
      (node (ref "JP15") (pin "1") (pinfunction "1_1") (pintype "passive"))
      (node (ref "JP15") (pin "2") (pinfunction "2_2") (pintype "passive"))
      (node (ref "JP7") (pin "1") (pinfunction "1_1") (pintype "passive"))
      (node (ref "JP8") (pin "1") (pinfunction "1_1") (pintype "passive"))
      (node (ref "JP9") (pin "1") (pinfunction "1_1") (pintype "passive"))
      (node (ref "R10") (pin "2") (pinfunction "2_2") (pintype "passive"))
      (node (ref "R11") (pin "2") (pinfunction "2_2") (pintype "passive"))
      (node (ref "R12") (pin "2") (pinfunction "2_2") (pintype "passive"))
      (node (ref "R13") (pin "2") (pinfunction "2_2") (pintype "passive"))
      (node (ref "R14") (pin "2") (pinfunction "2_2") (pintype "passive"))
      (node (ref "R19") (pin "2") (pinfunction "2_2") (pintype "passive"))
      (node (ref "R2") (pin "2") (pinfunction "2_2") (pintype "passive"))
      (node (ref "R20") (pin "2") (pinfunction "2_2") (pintype "passive"))
      (node (ref "R21") (pin "2") (pinfunction "2_2") (pintype "passive"))
      (node (ref "R22") (pin "2") (pinfunction "2_2") (pintype "passive"))
      (node (ref "R27") (pin "2") (pinfunction "2_2") (pintype "passive"))
      (node (ref "R4") (pin "2") (pinfunction "2_2") (pintype "passive"))
      (node (ref "R5") (pin "2") (pinfunction "2_2") (pintype "passive"))
      (node (ref "R6") (pin "2") (pinfunction "2_2") (pintype "passive"))
      (node (ref "R7") (pin "2") (pinfunction "2_2") (pintype "passive"))
      (node (ref "R8") (pin "2") (pinfunction "2_2") (pintype "passive"))
      (node (ref "R9") (pin "2") (pinfunction "2_2") (pintype "passive"))
    )
    (net (code "118") (name "unconnected-(JP2-Pad9)") (class "Default")
      (node (ref "JP2") (pin "9") (pinfunction "9_9") (pintype "passive"))
    )
    (net (code "119") (name "unconnected-(JP2-Pad10)") (class "Default")
      (node (ref "JP2") (pin "10") (pinfunction "10_10") (pintype "passive"))
    )
  )
)
